# 2layer_v3.net
KiCad netlist of a schematic drawn in EAGLE
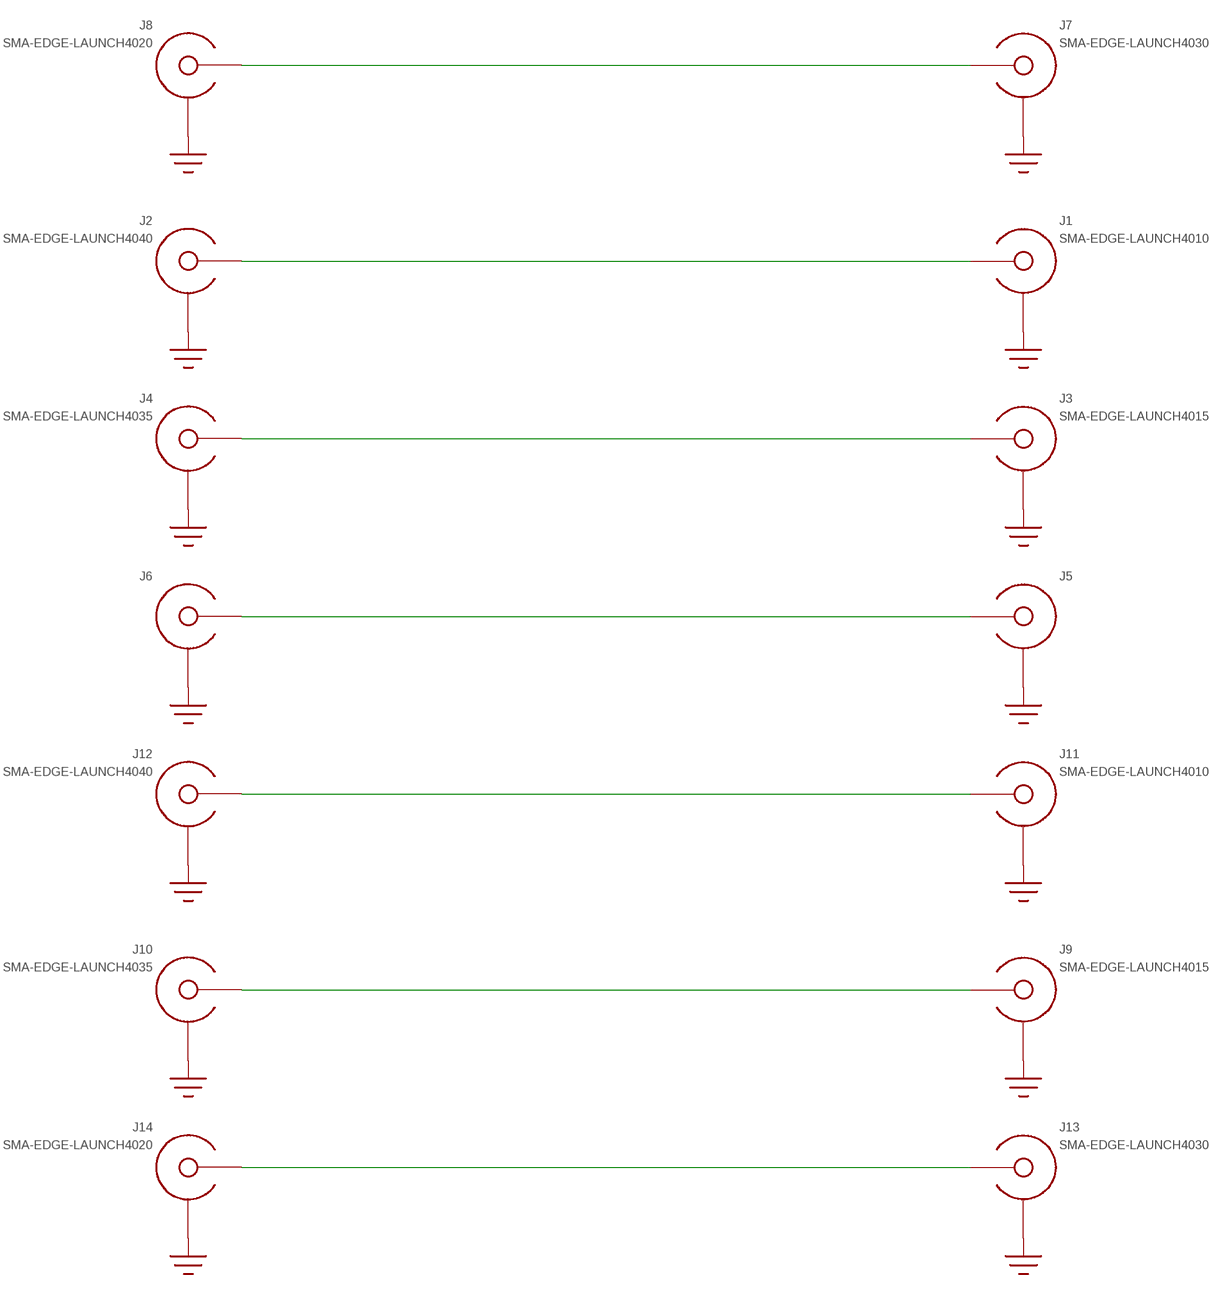
[diagram p0: schematic, sheet 1]

(export (version "E")
  (design (tool "Eeschema 10.0.6"))
  (components
    (comp (ref "J1")
      (value "SMA-EDGE-LAUNCH4010")
      (footprint "eagle-import:SMA_EDGE_LAUNCH_2L_4020_CUT_PIN")
      (libsource (lib "eagle-import") (part "SMA-EDGE-LAUNCHCUT-PIN"))
    )
    (comp (ref "J2")
      (value "SMA-EDGE-LAUNCH4040")
      (footprint "eagle-import:SMA_EDGE_LAUNCH_2L_4020_TAPER")
      (libsource (lib "eagle-import") (part "SMA-EDGE-LAUNCH4020_TAPER"))
    )
    (comp (ref "J3")
      (value "SMA-EDGE-LAUNCH4015")
      (footprint "eagle-import:SMA_EDGE_LAUNCH_2L_4020_CUT_PIN")
      (libsource (lib "eagle-import") (part "SMA-EDGE-LAUNCHCUT-PIN"))
    )
    (comp (ref "J4")
      (value "SMA-EDGE-LAUNCH4035")
      (footprint "eagle-import:SMA_EDGE_LAUNCH_2L_4020_TAPER")
      (libsource (lib "eagle-import") (part "SMA-EDGE-LAUNCH4020_TAPER"))
    )
    (comp (ref "J5")
      (value "SMA-EDGE-LAUNCHCUT-PIN")
      (footprint "eagle-import:SMA_EDGE_LAUNCH_2L_4020_CUT_PIN")
      (libsource (lib "eagle-import") (part "SMA-EDGE-LAUNCHCUT-PIN"))
    )
    (comp (ref "J6")
      (value "SMA-EDGE-LAUNCH4020_TAPER")
      (footprint "eagle-import:SMA_EDGE_LAUNCH_2L_4020_TAPER")
      (libsource (lib "eagle-import") (part "SMA-EDGE-LAUNCH4020_TAPER"))
    )
    (comp (ref "J7")
      (value "SMA-EDGE-LAUNCH4030")
      (footprint "eagle-import:SMA_EDGE_LAUNCH_2L_4020_CUT_PIN")
      (libsource (lib "eagle-import") (part "SMA-EDGE-LAUNCHCUT-PIN"))
    )
    (comp (ref "J8")
      (value "SMA-EDGE-LAUNCH4020")
      (footprint "eagle-import:SMA_EDGE_LAUNCH_2L_4020_TAPER")
      (libsource (lib "eagle-import") (part "SMA-EDGE-LAUNCH4020_TAPER"))
    )
    (comp (ref "J9")
      (value "SMA-EDGE-LAUNCH4015")
      (footprint "eagle-import:SMA_EDGE_LAUNCH_2L_4020_TAPER")
      (libsource (lib "eagle-import") (part "SMA-EDGE-LAUNCH4020_TAPER"))
    )
    (comp (ref "J10")
      (value "SMA-EDGE-LAUNCH4035")
      (footprint "eagle-import:SMA_EDGE_LAUNCH_2L_4020_CUT_PIN")
      (libsource (lib "eagle-import") (part "SMA-EDGE-LAUNCHCUT-PIN"))
    )
    (comp (ref "J11")
      (value "SMA-EDGE-LAUNCH4010")
      (footprint "eagle-import:SMA_EDGE_LAUNCH_2L_4020_TAPER")
      (libsource (lib "eagle-import") (part "SMA-EDGE-LAUNCH4020_TAPER"))
    )
    (comp (ref "J12")
      (value "SMA-EDGE-LAUNCH4040")
      (footprint "eagle-import:SMA_EDGE_LAUNCH_2L_4020_CUT_PIN")
      (libsource (lib "eagle-import") (part "SMA-EDGE-LAUNCHCUT-PIN"))
    )
    (comp (ref "J13")
      (value "SMA-EDGE-LAUNCH4030")
      (footprint "eagle-import:SMA_EDGE_LAUNCH_2L_4020_TAPER")
      (libsource (lib "eagle-import") (part "SMA-EDGE-LAUNCH4020_TAPER"))
    )
    (comp (ref "J14")
      (value "SMA-EDGE-LAUNCH4020")
      (footprint "eagle-import:SMA_EDGE_LAUNCH_2L_4020_CUT_PIN")
      (libsource (lib "eagle-import") (part "SMA-EDGE-LAUNCHCUT-PIN"))
    )
  )
  (nets
    (net (code "1") (name "GND") (class "Default")
      (node (ref "J1") (pin "BOTTOM_GND") (pinfunction "SHIELD_BOTTOM_GND") (pintype "bidirectional"))
      (node (ref "J1") (pin "GND@1") (pinfunction "SHIELD_GND@1") (pintype "bidirectional"))
      (node (ref "J1") (pin "GND@14") (pinfunction "SHIELD_GND@14") (pintype "bidirectional"))
      (node (ref "J1") (pin "GND@15") (pinfunction "SHIELD_GND@15") (pintype "bidirectional"))
      (node (ref "J1") (pin "GND@16") (pinfunction "SHIELD_GND@16") (pintype "bidirectional"))
      (node (ref "J1") (pin "GND@17") (pinfunction "SHIELD_GND@17") (pintype "bidirectional"))
      (node (ref "J1") (pin "GND@2") (pinfunction "SHIELD_GND@2") (pintype "bidirectional"))
      (node (ref "J1") (pin "GND@3") (pinfunction "SHIELD_GND@3") (pintype "bidirectional"))
      (node (ref "J1") (pin "GND@4") (pinfunction "SHIELD_GND@4") (pintype "bidirectional"))
      (node (ref "J1") (pin "GND@5") (pinfunction "SHIELD_GND@5") (pintype "bidirectional"))
      (node (ref "J1") (pin "GND@6") (pinfunction "SHIELD_GND@6") (pintype "bidirectional"))
      (node (ref "J1") (pin "GND@7") (pinfunction "SHIELD_GND@7") (pintype "bidirectional"))
      (node (ref "J1") (pin "GND@8") (pinfunction "SHIELD_GND@8") (pintype "bidirectional"))
      (node (ref "J1") (pin "GND_PAD1") (pinfunction "SHIELD_GND_PAD1") (pintype "bidirectional"))
      (node (ref "J1") (pin "GND_PAD2") (pinfunction "SHIELD_GND_PAD2") (pintype "bidirectional"))
      (node (ref "J10") (pin "BOTTOM_GND") (pinfunction "SHIELD_BOTTOM_GND") (pintype "bidirectional"))
      (node (ref "J10") (pin "GND@1") (pinfunction "SHIELD_GND@1") (pintype "bidirectional"))
      (node (ref "J10") (pin "GND@14") (pinfunction "SHIELD_GND@14") (pintype "bidirectional"))
      (node (ref "J10") (pin "GND@15") (pinfunction "SHIELD_GND@15") (pintype "bidirectional"))
      (node (ref "J10") (pin "GND@16") (pinfunction "SHIELD_GND@16") (pintype "bidirectional"))
      (node (ref "J10") (pin "GND@17") (pinfunction "SHIELD_GND@17") (pintype "bidirectional"))
      (node (ref "J10") (pin "GND@2") (pinfunction "SHIELD_GND@2") (pintype "bidirectional"))
      (node (ref "J10") (pin "GND@3") (pinfunction "SHIELD_GND@3") (pintype "bidirectional"))
      (node (ref "J10") (pin "GND@4") (pinfunction "SHIELD_GND@4") (pintype "bidirectional"))
      (node (ref "J10") (pin "GND@5") (pinfunction "SHIELD_GND@5") (pintype "bidirectional"))
      (node (ref "J10") (pin "GND@6") (pinfunction "SHIELD_GND@6") (pintype "bidirectional"))
      (node (ref "J10") (pin "GND@7") (pinfunction "SHIELD_GND@7") (pintype "bidirectional"))
      (node (ref "J10") (pin "GND@8") (pinfunction "SHIELD_GND@8") (pintype "bidirectional"))
      (node (ref "J10") (pin "GND_PAD1") (pinfunction "SHIELD_GND_PAD1") (pintype "bidirectional"))
      (node (ref "J10") (pin "GND_PAD2") (pinfunction "SHIELD_GND_PAD2") (pintype "bidirectional"))
      (node (ref "J11") (pin "BOTTOM_GND") (pinfunction "SHIELD_BOTTOM_GND") (pintype "bidirectional"))
      (node (ref "J11") (pin "GND@1") (pinfunction "SHIELD_GND@1") (pintype "bidirectional"))
      (node (ref "J11") (pin "GND@14") (pinfunction "SHIELD_GND@14") (pintype "bidirectional"))
      (node (ref "J11") (pin "GND@15") (pinfunction "SHIELD_GND@15") (pintype "bidirectional"))
      (node (ref "J11") (pin "GND@16") (pinfunction "SHIELD_GND@16") (pintype "bidirectional"))
      (node (ref "J11") (pin "GND@17") (pinfunction "SHIELD_GND@17") (pintype "bidirectional"))
      (node (ref "J11") (pin "GND@2") (pinfunction "SHIELD_GND@2") (pintype "bidirectional"))
      (node (ref "J11") (pin "GND@3") (pinfunction "SHIELD_GND@3") (pintype "bidirectional"))
      (node (ref "J11") (pin "GND@4") (pinfunction "SHIELD_GND@4") (pintype "bidirectional"))
      (node (ref "J11") (pin "GND@5") (pinfunction "SHIELD_GND@5") (pintype "bidirectional"))
      (node (ref "J11") (pin "GND@6") (pinfunction "SHIELD_GND@6") (pintype "bidirectional"))
      (node (ref "J11") (pin "GND@7") (pinfunction "SHIELD_GND@7") (pintype "bidirectional"))
      (node (ref "J11") (pin "GND@8") (pinfunction "SHIELD_GND@8") (pintype "bidirectional"))
      (node (ref "J11") (pin "GND_PAD1") (pinfunction "SHIELD_GND_PAD1") (pintype "bidirectional"))
      (node (ref "J11") (pin "GND_PAD2") (pinfunction "SHIELD_GND_PAD2") (pintype "bidirectional"))
      (node (ref "J11") (pin "P$1") (pinfunction "SHIELD_P$1") (pintype "bidirectional"))
      (node (ref "J11") (pin "P$2") (pinfunction "SHIELD_P$2") (pintype "bidirectional"))
      (node (ref "J12") (pin "BOTTOM_GND") (pinfunction "SHIELD_BOTTOM_GND") (pintype "bidirectional"))
      (node (ref "J12") (pin "GND@1") (pinfunction "SHIELD_GND@1") (pintype "bidirectional"))
      (node (ref "J12") (pin "GND@14") (pinfunction "SHIELD_GND@14") (pintype "bidirectional"))
      (node (ref "J12") (pin "GND@15") (pinfunction "SHIELD_GND@15") (pintype "bidirectional"))
      (node (ref "J12") (pin "GND@16") (pinfunction "SHIELD_GND@16") (pintype "bidirectional"))
      (node (ref "J12") (pin "GND@17") (pinfunction "SHIELD_GND@17") (pintype "bidirectional"))
      (node (ref "J12") (pin "GND@2") (pinfunction "SHIELD_GND@2") (pintype "bidirectional"))
      (node (ref "J12") (pin "GND@3") (pinfunction "SHIELD_GND@3") (pintype "bidirectional"))
      (node (ref "J12") (pin "GND@4") (pinfunction "SHIELD_GND@4") (pintype "bidirectional"))
      (node (ref "J12") (pin "GND@5") (pinfunction "SHIELD_GND@5") (pintype "bidirectional"))
      (node (ref "J12") (pin "GND@6") (pinfunction "SHIELD_GND@6") (pintype "bidirectional"))
      (node (ref "J12") (pin "GND@7") (pinfunction "SHIELD_GND@7") (pintype "bidirectional"))
      (node (ref "J12") (pin "GND@8") (pinfunction "SHIELD_GND@8") (pintype "bidirectional"))
      (node (ref "J12") (pin "GND_PAD1") (pinfunction "SHIELD_GND_PAD1") (pintype "bidirectional"))
      (node (ref "J12") (pin "GND_PAD2") (pinfunction "SHIELD_GND_PAD2") (pintype "bidirectional"))
      (node (ref "J13") (pin "BOTTOM_GND") (pinfunction "SHIELD_BOTTOM_GND") (pintype "bidirectional"))
      (node (ref "J13") (pin "GND@1") (pinfunction "SHIELD_GND@1") (pintype "bidirectional"))
      (node (ref "J13") (pin "GND@14") (pinfunction "SHIELD_GND@14") (pintype "bidirectional"))
      (node (ref "J13") (pin "GND@15") (pinfunction "SHIELD_GND@15") (pintype "bidirectional"))
      (node (ref "J13") (pin "GND@16") (pinfunction "SHIELD_GND@16") (pintype "bidirectional"))
      (node (ref "J13") (pin "GND@17") (pinfunction "SHIELD_GND@17") (pintype "bidirectional"))
      (node (ref "J13") (pin "GND@2") (pinfunction "SHIELD_GND@2") (pintype "bidirectional"))
      (node (ref "J13") (pin "GND@3") (pinfunction "SHIELD_GND@3") (pintype "bidirectional"))
      (node (ref "J13") (pin "GND@4") (pinfunction "SHIELD_GND@4") (pintype "bidirectional"))
      (node (ref "J13") (pin "GND@5") (pinfunction "SHIELD_GND@5") (pintype "bidirectional"))
      (node (ref "J13") (pin "GND@6") (pinfunction "SHIELD_GND@6") (pintype "bidirectional"))
      (node (ref "J13") (pin "GND@7") (pinfunction "SHIELD_GND@7") (pintype "bidirectional"))
      (node (ref "J13") (pin "GND@8") (pinfunction "SHIELD_GND@8") (pintype "bidirectional"))
      (node (ref "J13") (pin "GND_PAD1") (pinfunction "SHIELD_GND_PAD1") (pintype "bidirectional"))
      (node (ref "J13") (pin "GND_PAD2") (pinfunction "SHIELD_GND_PAD2") (pintype "bidirectional"))
      (node (ref "J13") (pin "P$1") (pinfunction "SHIELD_P$1") (pintype "bidirectional"))
      (node (ref "J13") (pin "P$2") (pinfunction "SHIELD_P$2") (pintype "bidirectional"))
      (node (ref "J14") (pin "BOTTOM_GND") (pinfunction "SHIELD_BOTTOM_GND") (pintype "bidirectional"))
      (node (ref "J14") (pin "GND@1") (pinfunction "SHIELD_GND@1") (pintype "bidirectional"))
      (node (ref "J14") (pin "GND@14") (pinfunction "SHIELD_GND@14") (pintype "bidirectional"))
      (node (ref "J14") (pin "GND@15") (pinfunction "SHIELD_GND@15") (pintype "bidirectional"))
      (node (ref "J14") (pin "GND@16") (pinfunction "SHIELD_GND@16") (pintype "bidirectional"))
      (node (ref "J14") (pin "GND@17") (pinfunction "SHIELD_GND@17") (pintype "bidirectional"))
      (node (ref "J14") (pin "GND@2") (pinfunction "SHIELD_GND@2") (pintype "bidirectional"))
      (node (ref "J14") (pin "GND@3") (pinfunction "SHIELD_GND@3") (pintype "bidirectional"))
      (node (ref "J14") (pin "GND@4") (pinfunction "SHIELD_GND@4") (pintype "bidirectional"))
      (node (ref "J14") (pin "GND@5") (pinfunction "SHIELD_GND@5") (pintype "bidirectional"))
      (node (ref "J14") (pin "GND@6") (pinfunction "SHIELD_GND@6") (pintype "bidirectional"))
      (node (ref "J14") (pin "GND@7") (pinfunction "SHIELD_GND@7") (pintype "bidirectional"))
      (node (ref "J14") (pin "GND@8") (pinfunction "SHIELD_GND@8") (pintype "bidirectional"))
      (node (ref "J14") (pin "GND_PAD1") (pinfunction "SHIELD_GND_PAD1") (pintype "bidirectional"))
      (node (ref "J14") (pin "GND_PAD2") (pinfunction "SHIELD_GND_PAD2") (pintype "bidirectional"))
      (node (ref "J2") (pin "BOTTOM_GND") (pinfunction "SHIELD_BOTTOM_GND") (pintype "bidirectional"))
      (node (ref "J2") (pin "GND@1") (pinfunction "SHIELD_GND@1") (pintype "bidirectional"))
      (node (ref "J2") (pin "GND@14") (pinfunction "SHIELD_GND@14") (pintype "bidirectional"))
      (node (ref "J2") (pin "GND@15") (pinfunction "SHIELD_GND@15") (pintype "bidirectional"))
      (node (ref "J2") (pin "GND@16") (pinfunction "SHIELD_GND@16") (pintype "bidirectional"))
      (node (ref "J2") (pin "GND@17") (pinfunction "SHIELD_GND@17") (pintype "bidirectional"))
      (node (ref "J2") (pin "GND@2") (pinfunction "SHIELD_GND@2") (pintype "bidirectional"))
      (node (ref "J2") (pin "GND@3") (pinfunction "SHIELD_GND@3") (pintype "bidirectional"))
      (node (ref "J2") (pin "GND@4") (pinfunction "SHIELD_GND@4") (pintype "bidirectional"))
      (node (ref "J2") (pin "GND@5") (pinfunction "SHIELD_GND@5") (pintype "bidirectional"))
      (node (ref "J2") (pin "GND@6") (pinfunction "SHIELD_GND@6") (pintype "bidirectional"))
      (node (ref "J2") (pin "GND@7") (pinfunction "SHIELD_GND@7") (pintype "bidirectional"))
      (node (ref "J2") (pin "GND@8") (pinfunction "SHIELD_GND@8") (pintype "bidirectional"))
      (node (ref "J2") (pin "GND_PAD1") (pinfunction "SHIELD_GND_PAD1") (pintype "bidirectional"))
      (node (ref "J2") (pin "GND_PAD2") (pinfunction "SHIELD_GND_PAD2") (pintype "bidirectional"))
      (node (ref "J2") (pin "P$1") (pinfunction "SHIELD_P$1") (pintype "bidirectional"))
      (node (ref "J2") (pin "P$2") (pinfunction "SHIELD_P$2") (pintype "bidirectional"))
      (node (ref "J3") (pin "BOTTOM_GND") (pinfunction "SHIELD_BOTTOM_GND") (pintype "bidirectional"))
      (node (ref "J3") (pin "GND@1") (pinfunction "SHIELD_GND@1") (pintype "bidirectional"))
      (node (ref "J3") (pin "GND@14") (pinfunction "SHIELD_GND@14") (pintype "bidirectional"))
      (node (ref "J3") (pin "GND@15") (pinfunction "SHIELD_GND@15") (pintype "bidirectional"))
      (node (ref "J3") (pin "GND@16") (pinfunction "SHIELD_GND@16") (pintype "bidirectional"))
      (node (ref "J3") (pin "GND@17") (pinfunction "SHIELD_GND@17") (pintype "bidirectional"))
      (node (ref "J3") (pin "GND@2") (pinfunction "SHIELD_GND@2") (pintype "bidirectional"))
      (node (ref "J3") (pin "GND@3") (pinfunction "SHIELD_GND@3") (pintype "bidirectional"))
      (node (ref "J3") (pin "GND@4") (pinfunction "SHIELD_GND@4") (pintype "bidirectional"))
      (node (ref "J3") (pin "GND@5") (pinfunction "SHIELD_GND@5") (pintype "bidirectional"))
      (node (ref "J3") (pin "GND@6") (pinfunction "SHIELD_GND@6") (pintype "bidirectional"))
      (node (ref "J3") (pin "GND@7") (pinfunction "SHIELD_GND@7") (pintype "bidirectional"))
      (node (ref "J3") (pin "GND@8") (pinfunction "SHIELD_GND@8") (pintype "bidirectional"))
      (node (ref "J3") (pin "GND_PAD1") (pinfunction "SHIELD_GND_PAD1") (pintype "bidirectional"))
      (node (ref "J3") (pin "GND_PAD2") (pinfunction "SHIELD_GND_PAD2") (pintype "bidirectional"))
      (node (ref "J4") (pin "BOTTOM_GND") (pinfunction "SHIELD_BOTTOM_GND") (pintype "bidirectional"))
      (node (ref "J4") (pin "GND@1") (pinfunction "SHIELD_GND@1") (pintype "bidirectional"))
      (node (ref "J4") (pin "GND@14") (pinfunction "SHIELD_GND@14") (pintype "bidirectional"))
      (node (ref "J4") (pin "GND@15") (pinfunction "SHIELD_GND@15") (pintype "bidirectional"))
      (node (ref "J4") (pin "GND@16") (pinfunction "SHIELD_GND@16") (pintype "bidirectional"))
      (node (ref "J4") (pin "GND@17") (pinfunction "SHIELD_GND@17") (pintype "bidirectional"))
      (node (ref "J4") (pin "GND@2") (pinfunction "SHIELD_GND@2") (pintype "bidirectional"))
      (node (ref "J4") (pin "GND@3") (pinfunction "SHIELD_GND@3") (pintype "bidirectional"))
      (node (ref "J4") (pin "GND@4") (pinfunction "SHIELD_GND@4") (pintype "bidirectional"))
      (node (ref "J4") (pin "GND@5") (pinfunction "SHIELD_GND@5") (pintype "bidirectional"))
      (node (ref "J4") (pin "GND@6") (pinfunction "SHIELD_GND@6") (pintype "bidirectional"))
      (node (ref "J4") (pin "GND@7") (pinfunction "SHIELD_GND@7") (pintype "bidirectional"))
      (node (ref "J4") (pin "GND@8") (pinfunction "SHIELD_GND@8") (pintype "bidirectional"))
      (node (ref "J4") (pin "GND_PAD1") (pinfunction "SHIELD_GND_PAD1") (pintype "bidirectional"))
      (node (ref "J4") (pin "GND_PAD2") (pinfunction "SHIELD_GND_PAD2") (pintype "bidirectional"))
      (node (ref "J4") (pin "P$1") (pinfunction "SHIELD_P$1") (pintype "bidirectional"))
      (node (ref "J4") (pin "P$2") (pinfunction "SHIELD_P$2") (pintype "bidirectional"))
      (node (ref "J5") (pin "BOTTOM_GND") (pinfunction "SHIELD_BOTTOM_GND") (pintype "bidirectional"))
      (node (ref "J5") (pin "GND@1") (pinfunction "SHIELD_GND@1") (pintype "bidirectional"))
      (node (ref "J5") (pin "GND@14") (pinfunction "SHIELD_GND@14") (pintype "bidirectional"))
      (node (ref "J5") (pin "GND@15") (pinfunction "SHIELD_GND@15") (pintype "bidirectional"))
      (node (ref "J5") (pin "GND@16") (pinfunction "SHIELD_GND@16") (pintype "bidirectional"))
      (node (ref "J5") (pin "GND@17") (pinfunction "SHIELD_GND@17") (pintype "bidirectional"))
      (node (ref "J5") (pin "GND@2") (pinfunction "SHIELD_GND@2") (pintype "bidirectional"))
      (node (ref "J5") (pin "GND@3") (pinfunction "SHIELD_GND@3") (pintype "bidirectional"))
      (node (ref "J5") (pin "GND@4") (pinfunction "SHIELD_GND@4") (pintype "bidirectional"))
      (node (ref "J5") (pin "GND@5") (pinfunction "SHIELD_GND@5") (pintype "bidirectional"))
      (node (ref "J5") (pin "GND@6") (pinfunction "SHIELD_GND@6") (pintype "bidirectional"))
      (node (ref "J5") (pin "GND@7") (pinfunction "SHIELD_GND@7") (pintype "bidirectional"))
      (node (ref "J5") (pin "GND@8") (pinfunction "SHIELD_GND@8") (pintype "bidirectional"))
      (node (ref "J5") (pin "GND_PAD1") (pinfunction "SHIELD_GND_PAD1") (pintype "bidirectional"))
      (node (ref "J5") (pin "GND_PAD2") (pinfunction "SHIELD_GND_PAD2") (pintype "bidirectional"))
      (node (ref "J6") (pin "BOTTOM_GND") (pinfunction "SHIELD_BOTTOM_GND") (pintype "bidirectional"))
      (node (ref "J6") (pin "GND@1") (pinfunction "SHIELD_GND@1") (pintype "bidirectional"))
      (node (ref "J6") (pin "GND@14") (pinfunction "SHIELD_GND@14") (pintype "bidirectional"))
      (node (ref "J6") (pin "GND@15") (pinfunction "SHIELD_GND@15") (pintype "bidirectional"))
      (node (ref "J6") (pin "GND@16") (pinfunction "SHIELD_GND@16") (pintype "bidirectional"))
      (node (ref "J6") (pin "GND@17") (pinfunction "SHIELD_GND@17") (pintype "bidirectional"))
      (node (ref "J6") (pin "GND@2") (pinfunction "SHIELD_GND@2") (pintype "bidirectional"))
      (node (ref "J6") (pin "GND@3") (pinfunction "SHIELD_GND@3") (pintype "bidirectional"))
      (node (ref "J6") (pin "GND@4") (pinfunction "SHIELD_GND@4") (pintype "bidirectional"))
      (node (ref "J6") (pin "GND@5") (pinfunction "SHIELD_GND@5") (pintype "bidirectional"))
      (node (ref "J6") (pin "GND@6") (pinfunction "SHIELD_GND@6") (pintype "bidirectional"))
      (node (ref "J6") (pin "GND@7") (pinfunction "SHIELD_GND@7") (pintype "bidirectional"))
      (node (ref "J6") (pin "GND@8") (pinfunction "SHIELD_GND@8") (pintype "bidirectional"))
      (node (ref "J6") (pin "GND_PAD1") (pinfunction "SHIELD_GND_PAD1") (pintype "bidirectional"))
      (node (ref "J6") (pin "GND_PAD2") (pinfunction "SHIELD_GND_PAD2") (pintype "bidirectional"))
      (node (ref "J6") (pin "P$1") (pinfunction "SHIELD_P$1") (pintype "bidirectional"))
      (node (ref "J6") (pin "P$2") (pinfunction "SHIELD_P$2") (pintype "bidirectional"))
      (node (ref "J7") (pin "BOTTOM_GND") (pinfunction "SHIELD_BOTTOM_GND") (pintype "bidirectional"))
      (node (ref "J7") (pin "GND@1") (pinfunction "SHIELD_GND@1") (pintype "bidirectional"))
      (node (ref "J7") (pin "GND@14") (pinfunction "SHIELD_GND@14") (pintype "bidirectional"))
      (node (ref "J7") (pin "GND@15") (pinfunction "SHIELD_GND@15") (pintype "bidirectional"))
      (node (ref "J7") (pin "GND@16") (pinfunction "SHIELD_GND@16") (pintype "bidirectional"))
      (node (ref "J7") (pin "GND@17") (pinfunction "SHIELD_GND@17") (pintype "bidirectional"))
      (node (ref "J7") (pin "GND@2") (pinfunction "SHIELD_GND@2") (pintype "bidirectional"))
      (node (ref "J7") (pin "GND@3") (pinfunction "SHIELD_GND@3") (pintype "bidirectional"))
      (node (ref "J7") (pin "GND@4") (pinfunction "SHIELD_GND@4") (pintype "bidirectional"))
      (node (ref "J7") (pin "GND@5") (pinfunction "SHIELD_GND@5") (pintype "bidirectional"))
      (node (ref "J7") (pin "GND@6") (pinfunction "SHIELD_GND@6") (pintype "bidirectional"))
      (node (ref "J7") (pin "GND@7") (pinfunction "SHIELD_GND@7") (pintype "bidirectional"))
      (node (ref "J7") (pin "GND@8") (pinfunction "SHIELD_GND@8") (pintype "bidirectional"))
      (node (ref "J7") (pin "GND_PAD1") (pinfunction "SHIELD_GND_PAD1") (pintype "bidirectional"))
      (node (ref "J7") (pin "GND_PAD2") (pinfunction "SHIELD_GND_PAD2") (pintype "bidirectional"))
      (node (ref "J8") (pin "BOTTOM_GND") (pinfunction "SHIELD_BOTTOM_GND") (pintype "bidirectional"))
      (node (ref "J8") (pin "GND@1") (pinfunction "SHIELD_GND@1") (pintype "bidirectional"))
      (node (ref "J8") (pin "GND@14") (pinfunction "SHIELD_GND@14") (pintype "bidirectional"))
      (node (ref "J8") (pin "GND@15") (pinfunction "SHIELD_GND@15") (pintype "bidirectional"))
      (node (ref "J8") (pin "GND@16") (pinfunction "SHIELD_GND@16") (pintype "bidirectional"))
      (node (ref "J8") (pin "GND@17") (pinfunction "SHIELD_GND@17") (pintype "bidirectional"))
      (node (ref "J8") (pin "GND@2") (pinfunction "SHIELD_GND@2") (pintype "bidirectional"))
      (node (ref "J8") (pin "GND@3") (pinfunction "SHIELD_GND@3") (pintype "bidirectional"))
      (node (ref "J8") (pin "GND@4") (pinfunction "SHIELD_GND@4") (pintype "bidirectional"))
      (node (ref "J8") (pin "GND@5") (pinfunction "SHIELD_GND@5") (pintype "bidirectional"))
      (node (ref "J8") (pin "GND@6") (pinfunction "SHIELD_GND@6") (pintype "bidirectional"))
      (node (ref "J8") (pin "GND@7") (pinfunction "SHIELD_GND@7") (pintype "bidirectional"))
      (node (ref "J8") (pin "GND@8") (pinfunction "SHIELD_GND@8") (pintype "bidirectional"))
      (node (ref "J8") (pin "GND_PAD1") (pinfunction "SHIELD_GND_PAD1") (pintype "bidirectional"))
      (node (ref "J8") (pin "GND_PAD2") (pinfunction "SHIELD_GND_PAD2") (pintype "bidirectional"))
      (node (ref "J8") (pin "P$1") (pinfunction "SHIELD_P$1") (pintype "bidirectional"))
      (node (ref "J8") (pin "P$2") (pinfunction "SHIELD_P$2") (pintype "bidirectional"))
      (node (ref "J9") (pin "BOTTOM_GND") (pinfunction "SHIELD_BOTTOM_GND") (pintype "bidirectional"))
      (node (ref "J9") (pin "GND@1") (pinfunction "SHIELD_GND@1") (pintype "bidirectional"))
      (node (ref "J9") (pin "GND@14") (pinfunction "SHIELD_GND@14") (pintype "bidirectional"))
      (node (ref "J9") (pin "GND@15") (pinfunction "SHIELD_GND@15") (pintype "bidirectional"))
      (node (ref "J9") (pin "GND@16") (pinfunction "SHIELD_GND@16") (pintype "bidirectional"))
      (node (ref "J9") (pin "GND@17") (pinfunction "SHIELD_GND@17") (pintype "bidirectional"))
      (node (ref "J9") (pin "GND@2") (pinfunction "SHIELD_GND@2") (pintype "bidirectional"))
      (node (ref "J9") (pin "GND@3") (pinfunction "SHIELD_GND@3") (pintype "bidirectional"))
      (node (ref "J9") (pin "GND@4") (pinfunction "SHIELD_GND@4") (pintype "bidirectional"))
      (node (ref "J9") (pin "GND@5") (pinfunction "SHIELD_GND@5") (pintype "bidirectional"))
      (node (ref "J9") (pin "GND@6") (pinfunction "SHIELD_GND@6") (pintype "bidirectional"))
      (node (ref "J9") (pin "GND@7") (pinfunction "SHIELD_GND@7") (pintype "bidirectional"))
      (node (ref "J9") (pin "GND@8") (pinfunction "SHIELD_GND@8") (pintype "bidirectional"))
      (node (ref "J9") (pin "GND_PAD1") (pinfunction "SHIELD_GND_PAD1") (pintype "bidirectional"))
      (node (ref "J9") (pin "GND_PAD2") (pinfunction "SHIELD_GND_PAD2") (pintype "bidirectional"))
      (node (ref "J9") (pin "P$1") (pinfunction "SHIELD_P$1") (pintype "bidirectional"))
      (node (ref "J9") (pin "P$2") (pinfunction "SHIELD_P$2") (pintype "bidirectional"))
    )
    (net (code "2") (name "Net-(J2-CENTER)") (class "Default")
      (node (ref "J1") (pin "CENTER@1") (pinfunction "CENTER_CENTER@1") (pintype "bidirectional"))
      (node (ref "J1") (pin "CENTER@3") (pinfunction "CENTER_CENTER@3") (pintype "bidirectional"))
      (node (ref "J2") (pin "CENTER@1") (pinfunction "CENTER_CENTER@1") (pintype "bidirectional"))
    )
    (net (code "3") (name "Net-(J4-CENTER)") (class "Default")
      (node (ref "J3") (pin "CENTER@1") (pinfunction "CENTER_CENTER@1") (pintype "bidirectional"))
      (node (ref "J3") (pin "CENTER@3") (pinfunction "CENTER_CENTER@3") (pintype "bidirectional"))
      (node (ref "J4") (pin "CENTER@1") (pinfunction "CENTER_CENTER@1") (pintype "bidirectional"))
    )
    (net (code "4") (name "Net-(J6-CENTER)") (class "Default")
      (node (ref "J5") (pin "CENTER@1") (pinfunction "CENTER_CENTER@1") (pintype "bidirectional"))
      (node (ref "J5") (pin "CENTER@3") (pinfunction "CENTER_CENTER@3") (pintype "bidirectional"))
      (node (ref "J6") (pin "CENTER@1") (pinfunction "CENTER_CENTER@1") (pintype "bidirectional"))
    )
    (net (code "5") (name "Net-(J8-CENTER)") (class "Default")
      (node (ref "J7") (pin "CENTER@1") (pinfunction "CENTER_CENTER@1") (pintype "bidirectional"))
      (node (ref "J7") (pin "CENTER@3") (pinfunction "CENTER_CENTER@3") (pintype "bidirectional"))
      (node (ref "J8") (pin "CENTER@1") (pinfunction "CENTER_CENTER@1") (pintype "bidirectional"))
    )
    (net (code "6") (name "Net-(J9-CENTER)") (class "Default")
      (node (ref "J10") (pin "CENTER@1") (pinfunction "CENTER_CENTER@1") (pintype "bidirectional"))
      (node (ref "J10") (pin "CENTER@3") (pinfunction "CENTER_CENTER@3") (pintype "bidirectional"))
      (node (ref "J9") (pin "CENTER@1") (pinfunction "CENTER_CENTER@1") (pintype "bidirectional"))
    )
    (net (code "7") (name "Net-(J11-CENTER)") (class "Default")
      (node (ref "J11") (pin "CENTER@1") (pinfunction "CENTER_CENTER@1") (pintype "bidirectional"))
      (node (ref "J12") (pin "CENTER@1") (pinfunction "CENTER_CENTER@1") (pintype "bidirectional"))
      (node (ref "J12") (pin "CENTER@3") (pinfunction "CENTER_CENTER@3") (pintype "bidirectional"))
    )
    (net (code "8") (name "Net-(J13-CENTER)") (class "Default")
      (node (ref "J13") (pin "CENTER@1") (pinfunction "CENTER_CENTER@1") (pintype "bidirectional"))
      (node (ref "J14") (pin "CENTER@1") (pinfunction "CENTER_CENTER@1") (pintype "bidirectional"))
      (node (ref "J14") (pin "CENTER@3") (pinfunction "CENTER_CENTER@3") (pintype "bidirectional"))
    )
  )
)
